# POWER-BOARD.net
KiCad netlist of a schematic drawn in Altium Designer
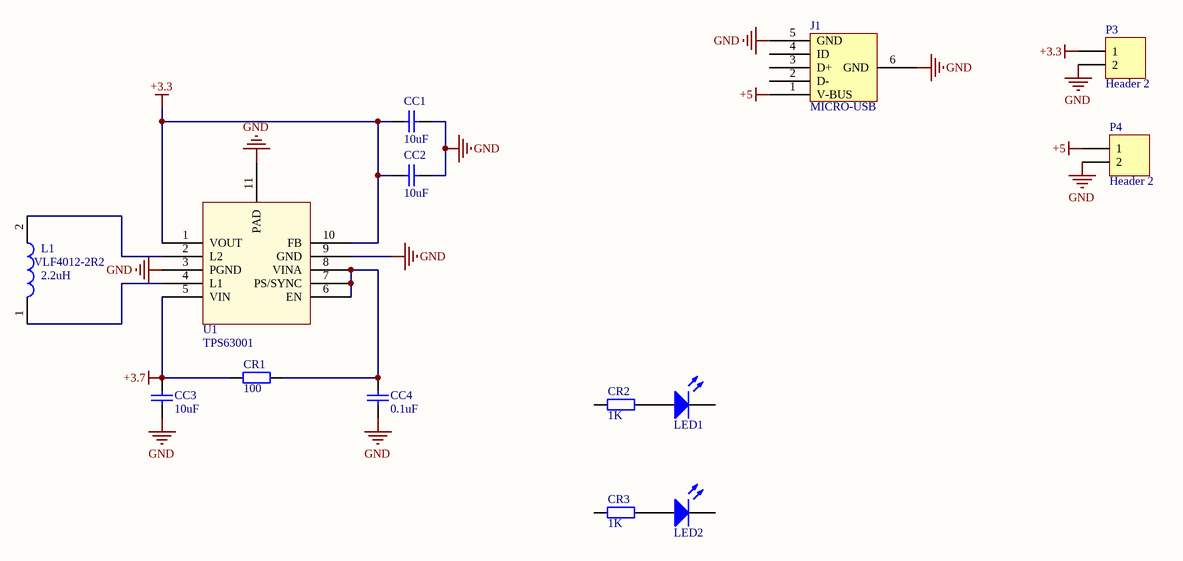
[diagram p0: POWER-BOARD.SchDoc]

(export (version "E")
  (design (tool "Eeschema 10.0.6"))
  (components
    (comp (ref "CC1")
      (value "10uF")
      (footprint "CC1608-0603")
      (description "Polarized Capacitor (Radial)")
      (fields (field (name "Comment") "Cap Chip 0603") (field (name "PUBLISHER") "Altium Limited"))
      (libsource (lib "EButterflyIntegratedLibrary") (part "Cap Chip 0603"))
    )
    (comp (ref "CC2")
      (value "10uF")
      (footprint "CC1608-0603")
      (description "Polarized Capacitor (Radial)")
      (fields (field (name "Comment") "Cap Chip 0603") (field (name "PUBLISHER") "Altium Limited"))
      (libsource (lib "EButterflyIntegratedLibrary") (part "Cap Chip 0603"))
    )
    (comp (ref "CC3")
      (value "10uF")
      (footprint "CC1608-0603")
      (description "Polarized Capacitor (Radial)")
      (fields (field (name "Comment") "Cap Chip 0603") (field (name "PUBLISHER") "Altium Limited"))
      (libsource (lib "EButterflyIntegratedLibrary") (part "Cap Chip 0603"))
    )
    (comp (ref "CC4")
      (value "0.1uF")
      (footprint "CC1005-0402")
      (description "Polarized Capacitor (Radial)")
      (fields (field (name "Comment") "Cap Chip 0402") (field (name "PUBLISHER") "Altium Limited"))
      (libsource (lib "EButterflyIntegratedLibrary") (part "Cap Chip 0402"))
    )
    (comp (ref "CR1")
      (value "100")
      (footprint "CR1005-0402")
      (description "Resistor")
      (fields (field (name "Comment") "Resistor Chip 0402") (field (name "PUBLISHER") "Altium Limited"))
      (libsource (lib "EButterflyIntegratedLibrary") (part "Resistor Chip 0402"))
    )
    (comp (ref "CR2")
      (value "1K")
      (footprint "CR1005-0402")
      (description "Resistor")
      (fields (field (name "Comment") "Resistor Chip 0402") (field (name "PUBLISHER") "Altium Limited"))
      (libsource (lib "EButterflyIntegratedLibrary") (part "Resistor Chip 0402"))
    )
    (comp (ref "CR3")
      (value "1K")
      (footprint "CR1005-0402")
      (description "Resistor")
      (fields (field (name "Comment") "Resistor Chip 0402") (field (name "PUBLISHER") "Altium Limited"))
      (libsource (lib "EButterflyIntegratedLibrary") (part "Resistor Chip 0402"))
    )
    (comp (ref "J1")
      (value "MICRO-USB")
      (footprint "MICRO-USB")
      (libsource (lib "EMOTION-GLASS") (part "MICRO-USB"))
    )
    (comp (ref "L1")
      (value "VLF4012-2R2")
      (footprint "VLF4012-2R2-INDUCTOR")
      (fields (field (name "L") "2.2uH"))
      (libsource (lib "EMOTION-GLASS") (part "VLF4012-2R2"))
    )
    (comp (ref "LED1")
      (value "LED Chip")
      (footprint "CLED1005-0402")
      (description "Typical Chip LED")
      (fields (field (name "PUBLISHER") "Altium Limited"))
      (libsource (lib "EButterflyIntegratedLibrary") (part "LED Chip"))
    )
    (comp (ref "LED2")
      (value "LED Chip")
      (footprint "CLED1005-0402")
      (description "Typical Chip LED")
      (fields (field (name "PUBLISHER") "Altium Limited"))
      (libsource (lib "EButterflyIntegratedLibrary") (part "LED Chip"))
    )
    (comp (ref "P3")
      (value "Header 2")
      (footprint "HDR1X2")
      (description "Header, 2-Pin")
      (fields (field (name "PUBLISHER") "Altium Limited"))
      (libsource (lib "EButterflyIntegratedLibrary") (part "Header 2"))
    )
    (comp (ref "P4")
      (value "Header 2")
      (footprint "HDR1X2")
      (description "Header, 2-Pin")
      (fields (field (name "PUBLISHER") "Altium Limited"))
      (libsource (lib "EButterflyIntegratedLibrary") (part "Header 2"))
    )
    (comp (ref "U1")
      (value "TPS63001")
      (footprint "TPS63001")
      (libsource (lib "EMOTION-GLASS") (part "TPS63001"))
    )
  )
  (nets
    (net (code "1") (name "+3.3") (class "Default")
      (node (ref "CC1") (pin "1") (pinfunction "1_1") (pintype "passive"))
      (node (ref "CC2") (pin "1") (pinfunction "1_1") (pintype "passive"))
      (node (ref "P3") (pin "1") (pinfunction "1_1") (pintype "passive"))
      (node (ref "U1") (pin "1") (pinfunction "VOUT_1") (pintype "passive"))
      (node (ref "U1") (pin "10") (pinfunction "FB_10") (pintype "passive"))
    )
    (net (code "2") (name "+3.7") (class "Default")
      (node (ref "CC3") (pin "2") (pinfunction "2_2") (pintype "passive"))
      (node (ref "CR1") (pin "1") (pinfunction "1_1") (pintype "passive"))
      (node (ref "U1") (pin "5") (pinfunction "VIN_5") (pintype "passive"))
    )
    (net (code "3") (name "+5") (class "Default")
      (node (ref "J1") (pin "1") (pinfunction "V-BUS_1") (pintype "passive"))
      (node (ref "P4") (pin "1") (pinfunction "1_1") (pintype "passive"))
    )
    (net (code "4") (name "GND") (class "Default")
      (node (ref "CC1") (pin "2") (pinfunction "2_2") (pintype "passive"))
      (node (ref "CC2") (pin "2") (pinfunction "2_2") (pintype "passive"))
      (node (ref "CC3") (pin "1") (pinfunction "1_1") (pintype "passive"))
      (node (ref "CC4") (pin "1") (pinfunction "1_1") (pintype "passive"))
      (node (ref "J1") (pin "5") (pinfunction "GND_5") (pintype "passive"))
      (node (ref "J1") (pin "6") (pinfunction "GND_6") (pintype "passive"))
      (node (ref "P3") (pin "2") (pinfunction "2_2") (pintype "passive"))
      (node (ref "P4") (pin "2") (pinfunction "2_2") (pintype "passive"))
      (node (ref "U1") (pin "11") (pinfunction "PAD_11") (pintype "passive"))
      (node (ref "U1") (pin "3") (pinfunction "PGND_3") (pintype "passive"))
      (node (ref "U1") (pin "9") (pinfunction "GND_9") (pintype "passive"))
    )
    (net (code "5") (name "Net-(LED1-A)") (class "Default")
      (node (ref "CR2") (pin "2") (pinfunction "2_2") (pintype "passive"))
      (node (ref "LED1") (pin "1") (pinfunction "A_1") (pintype "passive"))
    )
    (net (code "6") (name "Net-(LED2-A)") (class "Default")
      (node (ref "CR3") (pin "2") (pinfunction "2_2") (pintype "passive"))
      (node (ref "LED2") (pin "1") (pinfunction "A_1") (pintype "passive"))
    )
    (net (code "7") (name "Net-(U1-EN)") (class "Default")
      (node (ref "CC4") (pin "2") (pinfunction "2_2") (pintype "passive"))
      (node (ref "CR1") (pin "2") (pinfunction "2_2") (pintype "passive"))
      (node (ref "U1") (pin "6") (pinfunction "EN_6") (pintype "passive"))
      (node (ref "U1") (pin "7") (pinfunction "PS/SYNC_7") (pintype "passive"))
      (node (ref "U1") (pin "8") (pinfunction "VINA_8") (pintype "passive"))
    )
    (net (code "8") (name "Net-(U1-L1)") (class "Default")
      (node (ref "L1") (pin "1") (pintype "passive"))
      (node (ref "U1") (pin "4") (pinfunction "L1_4") (pintype "passive"))
    )
    (net (code "9") (name "Net-(U1-L2)") (class "Default")
      (node (ref "L1") (pin "2") (pintype "passive"))
      (node (ref "U1") (pin "2") (pinfunction "L2_2") (pintype "passive"))
    )
    (net (code "10") (name "unconnected-(CR2-Pad1)") (class "Default")
      (node (ref "CR2") (pin "1") (pinfunction "1_1") (pintype "passive"))
    )
    (net (code "11") (name "unconnected-(CR3-Pad1)") (class "Default")
      (node (ref "CR3") (pin "1") (pinfunction "1_1") (pintype "passive"))
    )
    (net (code "12") (name "unconnected-(J1-D+-Pad3)") (class "Default")
      (node (ref "J1") (pin "3") (pinfunction "D+_3") (pintype "passive"))
    )
    (net (code "13") (name "unconnected-(J1-D--Pad2)") (class "Default")
      (node (ref "J1") (pin "2") (pinfunction "D-_2") (pintype "passive"))
    )
    (net (code "14") (name "unconnected-(J1-ID-Pad4)") (class "Default")
      (node (ref "J1") (pin "4") (pinfunction "ID_4") (pintype "passive"))
    )
    (net (code "15") (name "unconnected-(LED1-K-Pad2)") (class "Default")
      (node (ref "LED1") (pin "2") (pinfunction "K_2") (pintype "passive"))
    )
    (net (code "16") (name "unconnected-(LED2-K-Pad2)") (class "Default")
      (node (ref "LED2") (pin "2") (pinfunction "K_2") (pintype "passive"))
    )
  )
)
